# sunalsorises.net
KiCad netlist of a schematic drawn in Altium Designer
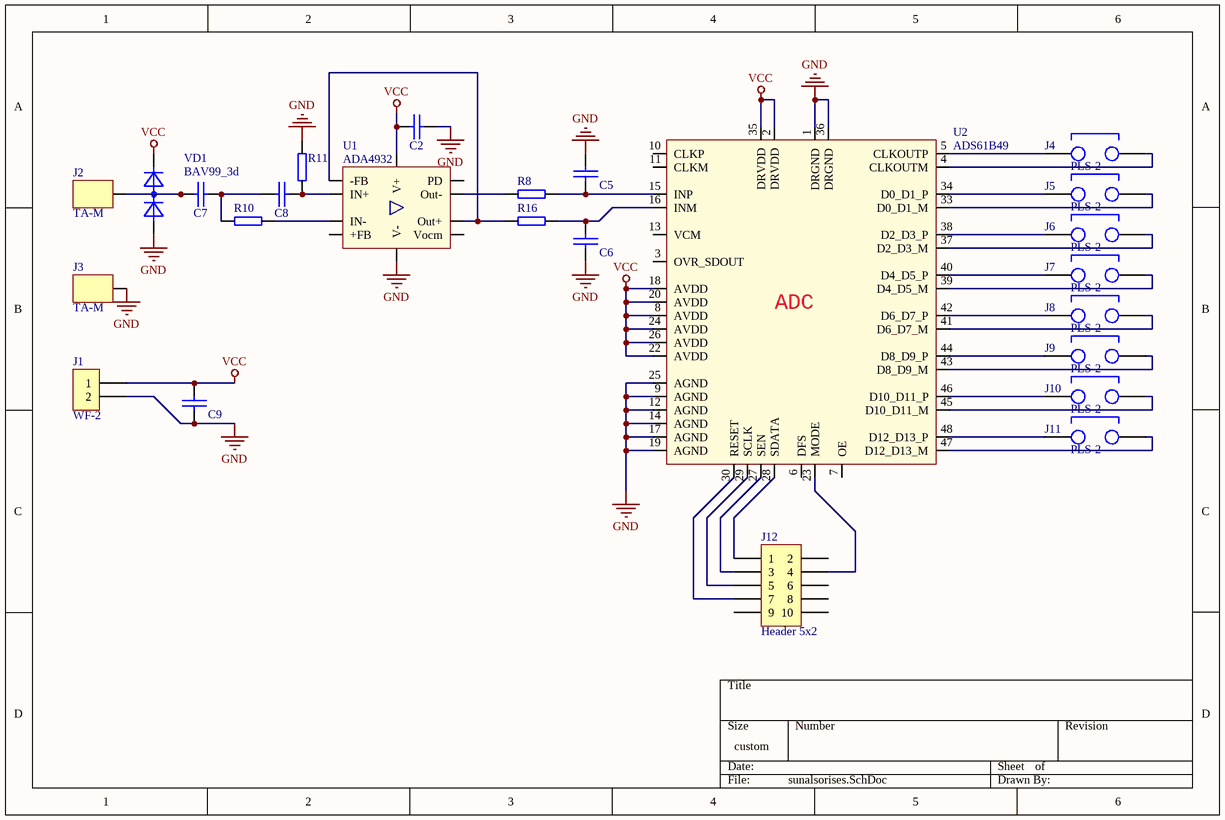
[diagram p0: sunalsorises.SchDoc]

(export (version "E")
  (design (tool "Eeschema 10.0.6"))
  (components
    (comp (ref "C2")
      (value "CAP_0805")
      (footprint "CAP_0805")
      (libsource (lib "sunalsorises") (part "CAP_0805"))
    )
    (comp (ref "C5")
      (value "CAP_0805")
      (footprint "CAP_0805")
      (libsource (lib "sunalsorises") (part "CAP_0805"))
    )
    (comp (ref "C6")
      (value "CAP_0805")
      (footprint "CAP_0805")
      (libsource (lib "sunalsorises") (part "CAP_0805"))
    )
    (comp (ref "C7")
      (value "CAP_0805")
      (footprint "CAP_0805")
      (libsource (lib "sunalsorises") (part "CAP_0805"))
    )
    (comp (ref "C8")
      (value "CAP_0805")
      (footprint "CAP_0805")
      (libsource (lib "sunalsorises") (part "CAP_0805"))
    )
    (comp (ref "C9")
      (value "CAP_0805")
      (footprint "CAP_0805")
      (libsource (lib "sunalsorises") (part "CAP_0805"))
    )
    (comp (ref "J1") (value "WF-2") (footprint "WF-2") (libsource (lib "sunalsorises") (part "WF-2")))
    (comp (ref "J2") (value "TA-M") (footprint "TA-M") (libsource (lib "sunalsorises") (part "TA-M")))
    (comp (ref "J3") (value "TA-M") (footprint "TA-M") (libsource (lib "sunalsorises") (part "TA-M")))
    (comp (ref "J4") (value "PLS-2") (footprint "PLS-2") (libsource (lib "sunalsorises") (part "PLS-2")))
    (comp (ref "J5") (value "PLS-2") (footprint "PLS-2") (libsource (lib "sunalsorises") (part "PLS-2")))
    (comp (ref "J6") (value "PLS-2") (footprint "PLS-2") (libsource (lib "sunalsorises") (part "PLS-2")))
    (comp (ref "J7") (value "PLS-2") (footprint "PLS-2") (libsource (lib "sunalsorises") (part "PLS-2")))
    (comp (ref "J8") (value "PLS-2") (footprint "PLS-2") (libsource (lib "sunalsorises") (part "PLS-2")))
    (comp (ref "J9") (value "PLS-2") (footprint "PLS-2") (libsource (lib "sunalsorises") (part "PLS-2")))
    (comp (ref "J10") (value "PLS-2") (footprint "PLS-2") (libsource (lib "sunalsorises") (part "PLS-2")))
    (comp (ref "J11") (value "PLS-2") (footprint "PLS-2") (libsource (lib "sunalsorises") (part "PLS-2")))
    (comp (ref "J12")
      (value "Header 5x2")
      (footprint "Header 5x2")
      (libsource (lib "sunalsorises") (part "Header 5x2"))
    )
    (comp (ref "R8") (value "~") (footprint "RES_0805") (libsource (lib "sunalsorises") (part "RES_0805")))
    (comp (ref "R10") (value "~") (footprint "RES_0805") (libsource (lib "sunalsorises") (part "RES_0805")))
    (comp (ref "R11") (value "~") (footprint "RES_0805") (libsource (lib "sunalsorises") (part "RES_0805")))
    (comp (ref "R16") (value "~") (footprint "RES_0805") (libsource (lib "sunalsorises") (part "RES_0805")))
    (comp (ref "U1")
      (value "ADA4932")
      (footprint "ADA4932")
      (libsource (lib "sunalsorises") (part "ADA4932"))
    )
    (comp (ref "U2")
      (value "ADS61B49")
      (footprint "ADS61B49")
      (libsource (lib "sunalsorises") (part "ADS61B49"))
    )
    (comp (ref "VD1")
      (value "BAV99_3d")
      (footprint "SOT-23 - 3d")
      (libsource (lib "sunalsorises") (part "BAV99_3d"))
    )
  )
  (nets
    (net (code "1") (name "GND") (class "Default")
      (node (ref "C2") (pin "2") (pintype "passive"))
      (node (ref "C5") (pin "1") (pintype "passive"))
      (node (ref "C6") (pin "2") (pintype "passive"))
      (node (ref "C9") (pin "2") (pintype "passive"))
      (node (ref "J1") (pin "2") (pinfunction "2_2") (pintype "passive"))
      (node (ref "J3") (pin "1") (pinfunction "1_1") (pintype "passive"))
      (node (ref "R11") (pin "2") (pinfunction "2_2") (pintype "passive"))
      (node (ref "U1") (pin "13") (pinfunction "V-_13") (pintype "passive"))
      (node (ref "U2") (pin "1") (pinfunction "DRGND_1") (pintype "passive"))
      (node (ref "U2") (pin "12") (pinfunction "AGND_12") (pintype "passive"))
      (node (ref "U2") (pin "14") (pinfunction "AGND_14") (pintype "passive"))
      (node (ref "U2") (pin "17") (pinfunction "AGND_17") (pintype "passive"))
      (node (ref "U2") (pin "19") (pinfunction "AGND_19") (pintype "passive"))
      (node (ref "U2") (pin "25") (pinfunction "AGND_25") (pintype "passive"))
      (node (ref "U2") (pin "36") (pinfunction "DRGND_36") (pintype "passive"))
      (node (ref "U2") (pin "9") (pinfunction "AGND_9") (pintype "passive"))
      (node (ref "VD1") (pin "1") (pinfunction "1_1") (pintype "passive"))
    )
    (net (code "2") (name "Net-(C7-Pad1)") (class "Default")
      (node (ref "C7") (pin "1") (pintype "passive"))
      (node (ref "J2") (pin "1") (pinfunction "1_1") (pintype "passive"))
      (node (ref "VD1") (pin "3") (pinfunction "3_3") (pintype "passive"))
    )
    (net (code "3") (name "Net-(C7-Pad2)") (class "Default")
      (node (ref "C7") (pin "2") (pintype "passive"))
      (node (ref "C8") (pin "1") (pintype "passive"))
      (node (ref "R10") (pin "1") (pinfunction "1_1") (pintype "passive"))
    )
    (net (code "4") (name "Net-(U1--FB)") (class "Default")
      (node (ref "R16") (pin "1") (pinfunction "1_1") (pintype "passive"))
      (node (ref "U1") (pin "1") (pinfunction "-FB_1") (pintype "passive"))
      (node (ref "U1") (pin "10") (pinfunction "Out+_10") (pintype "passive"))
    )
    (net (code "5") (name "Net-(U1-IN+)") (class "Default")
      (node (ref "C8") (pin "2") (pintype "passive"))
      (node (ref "R11") (pin "1") (pinfunction "1_1") (pintype "passive"))
      (node (ref "U1") (pin "2") (pinfunction "IN+_2") (pintype "passive"))
    )
    (net (code "6") (name "Net-(U1-IN-)") (class "Default")
      (node (ref "R10") (pin "2") (pinfunction "2_2") (pintype "passive"))
      (node (ref "U1") (pin "3") (pinfunction "IN-_3") (pintype "passive"))
    )
    (net (code "7") (name "Net-(U1-Out-)") (class "Default")
      (node (ref "R8") (pin "1") (pinfunction "1_1") (pintype "passive"))
      (node (ref "U1") (pin "11") (pinfunction "Out-_11") (pintype "passive"))
    )
    (net (code "8") (name "Net-(U2-CLKOUTM)") (class "Default")
      (node (ref "J4") (pin "2") (pinfunction "2_2") (pintype "passive"))
      (node (ref "U2") (pin "4") (pinfunction "CLKOUTM_4") (pintype "passive"))
    )
    (net (code "9") (name "Net-(U2-CLKOUTP)") (class "Default")
      (node (ref "J4") (pin "1") (pinfunction "1_1") (pintype "passive"))
      (node (ref "U2") (pin "5") (pinfunction "CLKOUTP_5") (pintype "passive"))
    )
    (net (code "10") (name "Net-(U2-D0_D1_M)") (class "Default")
      (node (ref "J5") (pin "2") (pinfunction "2_2") (pintype "passive"))
      (node (ref "U2") (pin "33") (pinfunction "D0_D1_M_33") (pintype "passive"))
    )
    (net (code "11") (name "Net-(U2-D0_D1_P)") (class "Default")
      (node (ref "J5") (pin "1") (pinfunction "1_1") (pintype "passive"))
      (node (ref "U2") (pin "34") (pinfunction "D0_D1_P_34") (pintype "passive"))
    )
    (net (code "12") (name "Net-(U2-D2_D3_M)") (class "Default")
      (node (ref "J6") (pin "2") (pinfunction "2_2") (pintype "passive"))
      (node (ref "U2") (pin "37") (pinfunction "D2_D3_M_37") (pintype "passive"))
    )
    (net (code "13") (name "Net-(U2-D2_D3_P)") (class "Default")
      (node (ref "J6") (pin "1") (pinfunction "1_1") (pintype "passive"))
      (node (ref "U2") (pin "38") (pinfunction "D2_D3_P_38") (pintype "passive"))
    )
    (net (code "14") (name "Net-(U2-D4_D5_M)") (class "Default")
      (node (ref "J7") (pin "2") (pinfunction "2_2") (pintype "passive"))
      (node (ref "U2") (pin "39") (pinfunction "D4_D5_M_39") (pintype "passive"))
    )
    (net (code "15") (name "Net-(U2-D4_D5_P)") (class "Default")
      (node (ref "J7") (pin "1") (pinfunction "1_1") (pintype "passive"))
      (node (ref "U2") (pin "40") (pinfunction "D4_D5_P_40") (pintype "passive"))
    )
    (net (code "16") (name "Net-(U2-D6_D7_M)") (class "Default")
      (node (ref "J8") (pin "2") (pinfunction "2_2") (pintype "passive"))
      (node (ref "U2") (pin "41") (pinfunction "D6_D7_M_41") (pintype "passive"))
    )
    (net (code "17") (name "Net-(U2-D6_D7_P)") (class "Default")
      (node (ref "J8") (pin "1") (pinfunction "1_1") (pintype "passive"))
      (node (ref "U2") (pin "42") (pinfunction "D6_D7_P_42") (pintype "passive"))
    )
    (net (code "18") (name "Net-(U2-D8_D9_M)") (class "Default")
      (node (ref "J9") (pin "2") (pinfunction "2_2") (pintype "passive"))
      (node (ref "U2") (pin "43") (pinfunction "D8_D9_M_43") (pintype "passive"))
    )
    (net (code "19") (name "Net-(U2-D8_D9_P)") (class "Default")
      (node (ref "J9") (pin "1") (pinfunction "1_1") (pintype "passive"))
      (node (ref "U2") (pin "44") (pinfunction "D8_D9_P_44") (pintype "passive"))
    )
    (net (code "20") (name "Net-(U2-D10_D11_M)") (class "Default")
      (node (ref "J10") (pin "2") (pinfunction "2_2") (pintype "passive"))
      (node (ref "U2") (pin "45") (pinfunction "D10_D11_M_45") (pintype "passive"))
    )
    (net (code "21") (name "Net-(U2-D10_D11_P)") (class "Default")
      (node (ref "J10") (pin "1") (pinfunction "1_1") (pintype "passive"))
      (node (ref "U2") (pin "46") (pinfunction "D10_D11_P_46") (pintype "passive"))
    )
    (net (code "22") (name "Net-(U2-D12_D13_M)") (class "Default")
      (node (ref "J11") (pin "2") (pinfunction "2_2") (pintype "passive"))
      (node (ref "U2") (pin "47") (pinfunction "D12_D13_M_47") (pintype "passive"))
    )
    (net (code "23") (name "Net-(U2-D12_D13_P)") (class "Default")
      (node (ref "J11") (pin "1") (pinfunction "1_1") (pintype "passive"))
      (node (ref "U2") (pin "48") (pinfunction "D12_D13_P_48") (pintype "passive"))
    )
    (net (code "24") (name "Net-(U2-INM)") (class "Default")
      (node (ref "C6") (pin "1") (pintype "passive"))
      (node (ref "R16") (pin "2") (pinfunction "2_2") (pintype "passive"))
      (node (ref "U2") (pin "16") (pinfunction "INM_16") (pintype "passive"))
    )
    (net (code "25") (name "Net-(U2-INP)") (class "Default")
      (node (ref "C5") (pin "2") (pintype "passive"))
      (node (ref "R8") (pin "2") (pinfunction "2_2") (pintype "passive"))
      (node (ref "U2") (pin "15") (pinfunction "INP_15") (pintype "passive"))
    )
    (net (code "26") (name "Net-(U2-MODE)") (class "Default")
      (node (ref "J12") (pin "4") (pinfunction "4_4") (pintype "passive"))
      (node (ref "U2") (pin "23") (pinfunction "MODE_23") (pintype "passive"))
    )
    (net (code "27") (name "Net-(U2-RESET)") (class "Default")
      (node (ref "J12") (pin "7") (pinfunction "7_7") (pintype "passive"))
      (node (ref "U2") (pin "30") (pinfunction "RESET_30") (pintype "passive"))
    )
    (net (code "28") (name "Net-(U2-SCLK)") (class "Default")
      (node (ref "J12") (pin "5") (pinfunction "5_5") (pintype "passive"))
      (node (ref "U2") (pin "29") (pinfunction "SCLK_29") (pintype "passive"))
    )
    (net (code "29") (name "Net-(U2-SDATA)") (class "Default")
      (node (ref "J12") (pin "1") (pinfunction "1_1") (pintype "passive"))
      (node (ref "U2") (pin "28") (pinfunction "SDATA_28") (pintype "passive"))
    )
    (net (code "30") (name "Net-(U2-SEN)") (class "Default")
      (node (ref "J12") (pin "3") (pinfunction "3_3") (pintype "passive"))
      (node (ref "U2") (pin "27") (pinfunction "SEN_27") (pintype "passive"))
    )
    (net (code "31") (name "VCC") (class "Default")
      (node (ref "C2") (pin "1") (pintype "passive"))
      (node (ref "C9") (pin "1") (pintype "passive"))
      (node (ref "J1") (pin "1") (pinfunction "1_1") (pintype "passive"))
      (node (ref "U1") (pin "5") (pinfunction "V+_5") (pintype "passive"))
      (node (ref "U2") (pin "18") (pinfunction "AVDD_18") (pintype "passive"))
      (node (ref "U2") (pin "2") (pinfunction "DRVDD_2") (pintype "passive"))
      (node (ref "U2") (pin "20") (pinfunction "AVDD_20") (pintype "passive"))
      (node (ref "U2") (pin "22") (pinfunction "AVDD_22") (pintype "passive"))
      (node (ref "U2") (pin "24") (pinfunction "AVDD_24") (pintype "passive"))
      (node (ref "U2") (pin "26") (pinfunction "AVDD_26") (pintype "passive"))
      (node (ref "U2") (pin "35") (pinfunction "DRVDD_35") (pintype "passive"))
      (node (ref "U2") (pin "8") (pinfunction "AVDD_8") (pintype "passive"))
      (node (ref "VD1") (pin "2") (pinfunction "2_2") (pintype "passive"))
    )
    (net (code "32") (name "unconnected-(J12-Pad2)") (class "Default")
      (node (ref "J12") (pin "2") (pinfunction "2_2") (pintype "passive"))
    )
    (net (code "33") (name "unconnected-(J12-Pad6)") (class "Default")
      (node (ref "J12") (pin "6") (pinfunction "6_6") (pintype "passive"))
    )
    (net (code "34") (name "unconnected-(J12-Pad8)") (class "Default")
      (node (ref "J12") (pin "8") (pinfunction "8_8") (pintype "passive"))
    )
    (net (code "35") (name "unconnected-(J12-Pad9)") (class "Default")
      (node (ref "J12") (pin "9") (pinfunction "9_9") (pintype "passive"))
    )
    (net (code "36") (name "unconnected-(J12-Pad10)") (class "Default")
      (node (ref "J12") (pin "10") (pinfunction "10_10") (pintype "passive"))
    )
    (net (code "37") (name "unconnected-(U1-+FB-Pad4)") (class "Default")
      (node (ref "U1") (pin "4") (pinfunction "+FB_4") (pintype "passive"))
    )
    (net (code "38") (name "unconnected-(U1-PD-Pad12)") (class "Default")
      (node (ref "U1") (pin "12") (pinfunction "PD_12") (pintype "passive"))
    )
    (net (code "39") (name "unconnected-(U1-Vocm-Pad9)") (class "Default")
      (node (ref "U1") (pin "9") (pinfunction "Vocm_9") (pintype "passive"))
    )
    (net (code "40") (name "unconnected-(U2-CLKM-Pad11)") (class "Default")
      (node (ref "U2") (pin "11") (pinfunction "CLKM_11") (pintype "passive"))
    )
    (net (code "41") (name "unconnected-(U2-CLKP-Pad10)") (class "Default")
      (node (ref "U2") (pin "10") (pinfunction "CLKP_10") (pintype "passive"))
    )
    (net (code "42") (name "unconnected-(U2-DFS-Pad6)") (class "Default")
      (node (ref "U2") (pin "6") (pinfunction "DFS_6") (pintype "passive"))
    )
    (net (code "43") (name "unconnected-(U2-OE-Pad7)") (class "Default")
      (node (ref "U2") (pin "7") (pinfunction "OE_7") (pintype "passive"))
    )
    (net (code "44") (name "unconnected-(U2-OVR_SDOUT-Pad3)") (class "Default")
      (node (ref "U2") (pin "3") (pinfunction "OVR_SDOUT_3") (pintype "passive"))
    )
    (net (code "45") (name "unconnected-(U2-VCM-Pad13)") (class "Default")
      (node (ref "U2") (pin "13") (pinfunction "VCM_13") (pintype "passive"))
    )
  )
)
